# BLDC_ext.net
KiCad netlist of a schematic drawn in Altium Designer
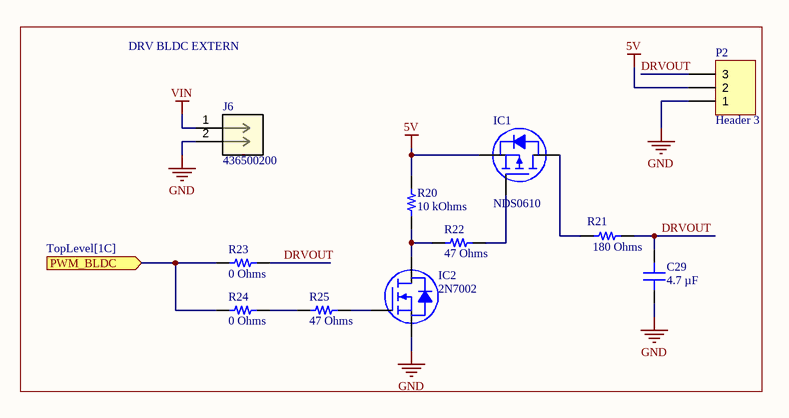
[diagram p0: BLDC_ext.SchDoc]

(export (version "E")
  (design (tool "Eeschema 10.0.6"))
  (components
    (comp (ref "C29")
      (value "4.7 µF")
      (footprint "CAP 0805_2012")
      (description "CAP CER 4.7UF 6.3V X7R 0805")
      (fields (field (name "PART NUMBER") "C0805X475J9RACAUTO") (field (name "MANUFACTURER") "KEMET"))
      (libsource (lib "Celestial Altium Library - altium_library") (part "Capacitor"))
    )
    (comp (ref "IC1")
      (value "NDS0610")
      (footprint "ON SEMI SOT-23-3")
      (description "MOSFET P-CH 60V 120MA SOT-23")
      (fields (field (name "MANUFACTURER") "ON Semiconductor"))
      (libsource (lib "Celestial Altium Library - altium_library") (part "ON SEMI MOSFET P-CH SOT-23-3"))
    )
    (comp (ref "IC2")
      (value "2N7002")
      (footprint "ON SEMI SOT-23-3")
      (description "MOSFET N-CH 60V 115MA SOT-23")
      (fields (field (name "MANUFACTURER") "ON Semiconductor"))
      (libsource (lib "Celestial Altium Library - altium_library") (part "ON SEMI MOSFET N-CH SOT-23-3"))
    )
    (comp (ref "J6")
      (value "436500200")
      (footprint "CONN_SD-43650-001_02_MOL")
      (description "No Description Available")
      (libsource (lib "436500200") (part "436500200"))
    )
    (comp (ref "P2")
      (value "Header 3")
      (footprint "HDR1X3")
      (description "Header, 3-Pin")
      (fields (field (name "PUBLISHER") "Altium Limited"))
      (libsource (lib "Miscellaneous Connectors") (part "Header 3"))
    )
    (comp (ref "R20")
      (value "10 kOhms")
      (footprint "YAGEO RES 0603_1608")
      (description "RES SMD 10K OHM 0.5% 1/10W 0603")
      (fields (field (name "PART NUMBER") "RT0603DRD0710KL") (field (name "MANUFACTURER") "Yageo"))
      (libsource (lib "Celestial Altium Library - altium_library") (part "Resistor"))
    )
    (comp (ref "R21")
      (value "180 Ohms")
      (footprint "YAGEO RES 0603_1608")
      (description "RES SMD 180 OHM 0.1% 1/10W 0603")
      (fields (field (name "PART NUMBER") "RT0603BRD07180RL") (field (name "MANUFACTURER") "Yageo"))
      (libsource (lib "Celestial Altium Library - altium_library") (part "Resistor"))
    )
    (comp (ref "R22")
      (value "47 Ohms")
      (footprint "YAGEO RES 0603_1608")
      (description "RES 47 OHM 5% 1/4W 0603")
      (fields (field (name "PART NUMBER") "SR0603JR-7T47RL") (field (name "MANUFACTURER") "Yageo"))
      (libsource (lib "Celestial Altium Library - altium_library") (part "Resistor"))
    )
    (comp (ref "R23")
      (value "0 Ohms")
      (footprint "YAGEO RES 0603_1608")
      (description "RES 0 OHM JUMPER 1/2W 0603")
      (fields (field (name "PART NUMBER") "PA0603-R-070RL") (field (name "MANUFACTURER") "Yageo"))
      (libsource (lib "Celestial Altium Library - altium_library") (part "Resistor"))
    )
    (comp (ref "R24")
      (value "0 Ohms")
      (footprint "YAGEO RES 0603_1608")
      (description "RES 0 OHM JUMPER 1/2W 0603")
      (fields (field (name "PART NUMBER") "PA0603-R-070RL") (field (name "MANUFACTURER") "Yageo"))
      (libsource (lib "Celestial Altium Library - altium_library") (part "Resistor"))
    )
    (comp (ref "R25")
      (value "47 Ohms")
      (footprint "YAGEO RES 0603_1608")
      (description "RES 47 OHM 5% 1/4W 0603")
      (fields (field (name "PART NUMBER") "SR0603JR-7T47RL") (field (name "MANUFACTURER") "Yageo"))
      (libsource (lib "Celestial Altium Library - altium_library") (part "Resistor"))
    )
  )
  (nets
    (net (code "1") (name "/DRVOUT") (class "Default")
      (node (ref "C29") (pin "2") (pinfunction "2_2") (pintype "passive"))
      (node (ref "P2") (pin "3") (pinfunction "3_3") (pintype "passive"))
      (node (ref "R21") (pin "2") (pinfunction "2_2") (pintype "passive"))
      (node (ref "R23") (pin "2") (pinfunction "2_2") (pintype "passive"))
    )
    (net (code "2") (name "/PWM_BLDC") (class "Default")
      (node (ref "R23") (pin "1") (pinfunction "1_1") (pintype "passive"))
      (node (ref "R24") (pin "1") (pinfunction "1_1") (pintype "passive"))
    )
    (net (code "3") (name "5V") (class "Default")
      (node (ref "IC1") (pin "2") (pinfunction "S_2") (pintype "passive"))
      (node (ref "P2") (pin "2") (pinfunction "2_2") (pintype "passive"))
      (node (ref "R20") (pin "2") (pinfunction "2_2") (pintype "passive"))
    )
    (net (code "4") (name "GND") (class "Default")
      (node (ref "C29") (pin "1") (pinfunction "1_1") (pintype "passive"))
      (node (ref "IC2") (pin "2") (pinfunction "S_2") (pintype "passive"))
      (node (ref "J6") (pin "2") (pinfunction "2_2") (pintype "passive"))
      (node (ref "P2") (pin "1") (pinfunction "1_1") (pintype "passive"))
    )
    (net (code "5") (name "Net-(IC1-D)") (class "Default")
      (node (ref "IC1") (pin "3") (pinfunction "D_3") (pintype "passive"))
      (node (ref "R21") (pin "1") (pinfunction "1_1") (pintype "passive"))
    )
    (net (code "6") (name "Net-(IC1-G)") (class "Default")
      (node (ref "IC1") (pin "1") (pinfunction "G_1") (pintype "passive"))
      (node (ref "R22") (pin "2") (pinfunction "2_2") (pintype "passive"))
    )
    (net (code "7") (name "Net-(IC2-D)") (class "Default")
      (node (ref "IC2") (pin "3") (pinfunction "D_3") (pintype "passive"))
      (node (ref "R20") (pin "1") (pinfunction "1_1") (pintype "passive"))
      (node (ref "R22") (pin "1") (pinfunction "1_1") (pintype "passive"))
    )
    (net (code "8") (name "Net-(IC2-G)") (class "Default")
      (node (ref "IC2") (pin "1") (pinfunction "G_1") (pintype "passive"))
      (node (ref "R25") (pin "2") (pinfunction "2_2") (pintype "passive"))
    )
    (net (code "9") (name "Net-(R24-Pad2)") (class "Default")
      (node (ref "R24") (pin "2") (pinfunction "2_2") (pintype "passive"))
      (node (ref "R25") (pin "1") (pinfunction "1_1") (pintype "passive"))
    )
    (net (code "10") (name "VIN") (class "Default")
      (node (ref "J6") (pin "1") (pinfunction "1_1") (pintype "passive"))
    )
  )
)
